# Barebones.net
KiCad netlist of a schematic drawn in EAGLE
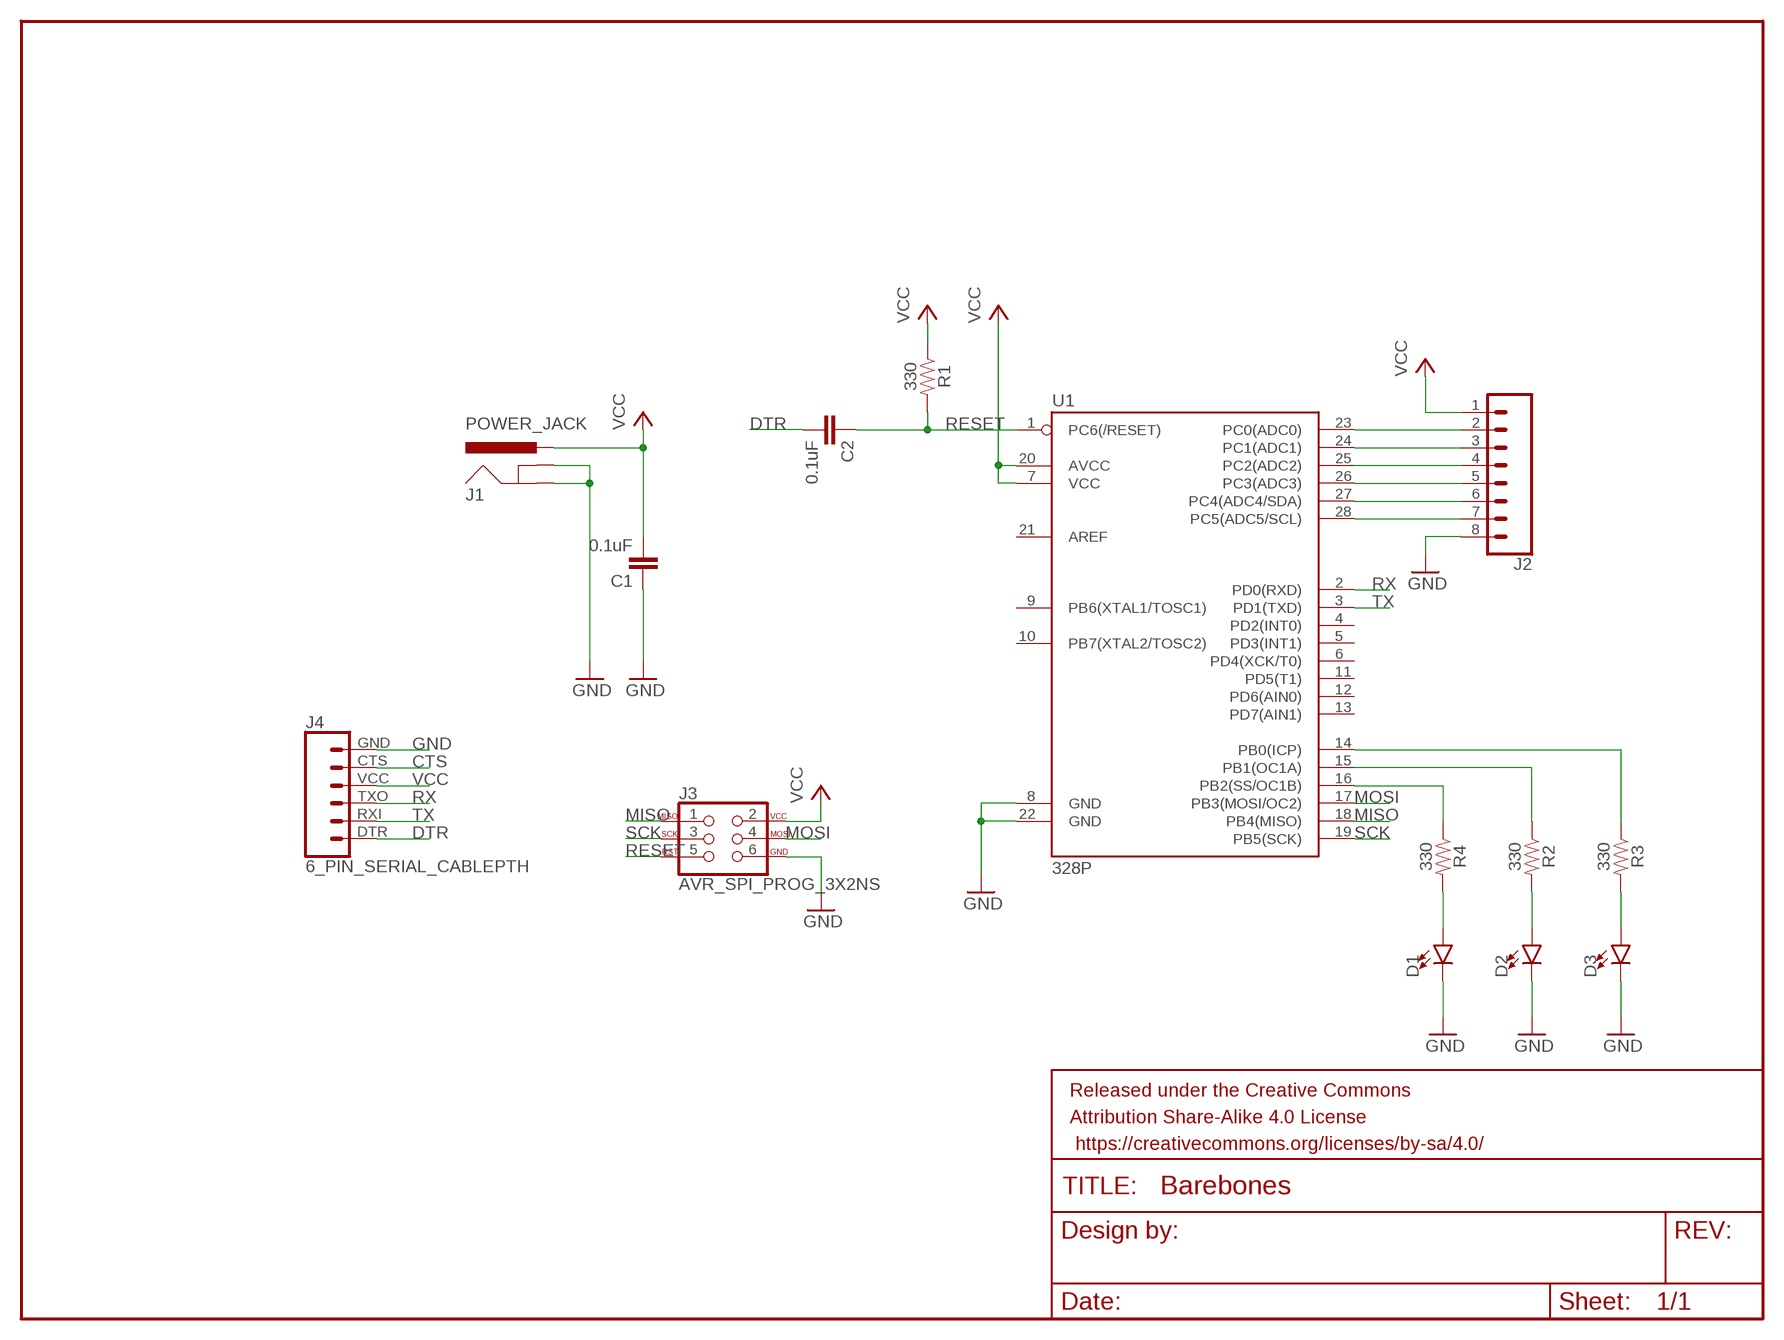
[diagram p0: schematic, sheet 1]

(export (version "E")
  (design (tool "Eeschema 10.0.6"))
  (components
    (comp (ref "C1")
      (value "0.1uF")
      (footprint "eagle-import:CAP-PTH-SMALL-KIT")
      (libsource (lib "eagle-import") (part "0.1UF-KIT-EZ-50V-20%"))
    )
    (comp (ref "C2")
      (value "0.1uF")
      (footprint "eagle-import:CAP-PTH-SMALL-KIT")
      (libsource (lib "eagle-import") (part "0.1UF-KIT-EZ-50V-20%"))
    )
    (comp (ref "D1")
      (value "LED5MM")
      (footprint "eagle-import:LED_5MM")
      (libsource (lib "eagle-import") (part "LED5MM"))
    )
    (comp (ref "D2")
      (value "LED5MM")
      (footprint "eagle-import:LED_5MM")
      (libsource (lib "eagle-import") (part "LED5MM"))
    )
    (comp (ref "D3")
      (value "LED5MM")
      (footprint "eagle-import:LED_5MM")
      (libsource (lib "eagle-import") (part "LED5MM"))
    )
    (comp (ref "FRAME1")
      (value "FRAME-LETTER")
      (footprint "eagle-import:CREATIVE_COMMONS")
      (libsource (lib "eagle-import") (part "FRAME-LETTER"))
    )
    (comp (ref "J1")
      (value "POWER_JACK")
      (footprint "eagle-import:POWER_JACK_PTH")
      (libsource (lib "eagle-import") (part "POWER_JACK"))
    )
    (comp (ref "J2")
      (value "CONN_08\"")
      (footprint "eagle-import:1X08")
      (libsource (lib "eagle-import") (part "CONN_08{dblquote}"))
    )
    (comp (ref "J3")
      (value "AVR_SPI_PROG_3X2NS")
      (footprint "eagle-import:2X3-NS")
      (libsource (lib "eagle-import") (part "AVR_SPI_PROG_3X2NS"))
    )
    (comp (ref "J4")
      (value "6_PIN_SERIAL_CABLEPTH")
      (footprint "eagle-import:FTDI_BASIC")
      (libsource (lib "eagle-import") (part "6_PIN_SERIAL_CABLEPTH"))
    )
    (comp (ref "R1")
      (value "330")
      (footprint "eagle-import:AXIAL-0.3")
      (libsource (lib "eagle-import") (part "330OHM-HORIZ-1/10W-5%"))
    )
    (comp (ref "R2")
      (value "330")
      (footprint "eagle-import:AXIAL-0.3")
      (libsource (lib "eagle-import") (part "330OHM-HORIZ-1/10W-5%"))
    )
    (comp (ref "R3")
      (value "330")
      (footprint "eagle-import:AXIAL-0.3")
      (libsource (lib "eagle-import") (part "330OHM-HORIZ-1/10W-5%"))
    )
    (comp (ref "R4")
      (value "330")
      (footprint "eagle-import:AXIAL-0.3")
      (libsource (lib "eagle-import") (part "330OHM-HORIZ-1/10W-5%"))
    )
    (comp (ref "U1")
      (value "328P")
      (footprint "eagle-import:DIP28")
      (libsource (lib "eagle-import") (part "ATMEGA328P_PDIP"))
    )
  )
  (nets
    (net (code "1") (name "/CTS") (class "Default")
      (node (ref "J4") (pin "CTS") (pinfunction "5_CTS") (pintype "passive"))
    )
    (net (code "2") (name "/DTR") (class "Default")
      (node (ref "C2") (pin "2") (pinfunction "2_2") (pintype "passive"))
      (node (ref "J4") (pin "DTR") (pinfunction "1_DTR") (pintype "passive"))
    )
    (net (code "3") (name "/MISO") (class "Default")
      (node (ref "J3") (pin "1") (pinfunction "1_1") (pintype "passive"))
      (node (ref "U1") (pin "18") (pinfunction "PB4(MISO)_18") (pintype "bidirectional"))
    )
    (net (code "4") (name "/MOSI") (class "Default")
      (node (ref "J3") (pin "4") (pinfunction "4_4") (pintype "passive"))
      (node (ref "U1") (pin "17") (pinfunction "PB3(MOSI/OC2)_17") (pintype "bidirectional"))
    )
    (net (code "5") (name "/RESET") (class "Default")
      (node (ref "C2") (pin "1") (pinfunction "1_1") (pintype "passive"))
      (node (ref "J3") (pin "5") (pinfunction "5_5") (pintype "passive"))
      (node (ref "R1") (pin "P$2") (pinfunction "2_P$2") (pintype "passive"))
      (node (ref "U1") (pin "1") (pinfunction "PC6(/RESET)_1") (pintype "bidirectional"))
    )
    (net (code "6") (name "/RX") (class "Default")
      (node (ref "J4") (pin "TXO") (pinfunction "3_TXO") (pintype "passive"))
      (node (ref "U1") (pin "2") (pinfunction "PD0(RXD)_2") (pintype "bidirectional"))
    )
    (net (code "7") (name "/SCK") (class "Default")
      (node (ref "J3") (pin "3") (pinfunction "3_3") (pintype "passive"))
      (node (ref "U1") (pin "19") (pinfunction "PB5(SCK)_19") (pintype "bidirectional"))
    )
    (net (code "8") (name "/TX") (class "Default")
      (node (ref "J4") (pin "RXI") (pinfunction "2_RXI") (pintype "passive"))
      (node (ref "U1") (pin "3") (pinfunction "PD1(TXD)_3") (pintype "bidirectional"))
    )
    (net (code "9") (name "GND") (class "Default")
      (node (ref "C1") (pin "1") (pinfunction "1_1") (pintype "passive"))
      (node (ref "D1") (pin "K") (pinfunction "C_K") (pintype "passive"))
      (node (ref "D2") (pin "K") (pinfunction "C_K") (pintype "passive"))
      (node (ref "D3") (pin "K") (pinfunction "C_K") (pintype "passive"))
      (node (ref "J1") (pin "GND") (pinfunction "GND_GND") (pintype "bidirectional"))
      (node (ref "J1") (pin "GNDBREAK") (pinfunction "GNDBREAK_GNDBREAK") (pintype "bidirectional"))
      (node (ref "J2") (pin "8") (pinfunction "8_8") (pintype "passive"))
      (node (ref "J3") (pin "6") (pinfunction "6_6") (pintype "passive"))
      (node (ref "J4") (pin "GND") (pinfunction "6_GND") (pintype "passive"))
      (node (ref "U1") (pin "22") (pinfunction "GND_22") (pintype "bidirectional"))
      (node (ref "U1") (pin "8") (pinfunction "GND_8") (pintype "bidirectional"))
    )
    (net (code "10") (name "Net-(R2-1)") (class "Default")
      (node (ref "R2") (pin "P$1") (pinfunction "1_P$1") (pintype "passive"))
      (node (ref "U1") (pin "15") (pinfunction "PB1(OC1A)_15") (pintype "bidirectional"))
    )
    (net (code "11") (name "Net-(R2-2)") (class "Default")
      (node (ref "D2") (pin "A") (pinfunction "A_A") (pintype "passive"))
      (node (ref "R2") (pin "P$2") (pinfunction "2_P$2") (pintype "passive"))
    )
    (net (code "12") (name "Net-(R3-1)") (class "Default")
      (node (ref "R3") (pin "P$1") (pinfunction "1_P$1") (pintype "passive"))
      (node (ref "U1") (pin "14") (pinfunction "PB0(ICP)_14") (pintype "bidirectional"))
    )
    (net (code "13") (name "Net-(R3-2)") (class "Default")
      (node (ref "D3") (pin "A") (pinfunction "A_A") (pintype "passive"))
      (node (ref "R3") (pin "P$2") (pinfunction "2_P$2") (pintype "passive"))
    )
    (net (code "14") (name "Net-(R4-1)") (class "Default")
      (node (ref "R4") (pin "P$1") (pinfunction "1_P$1") (pintype "passive"))
      (node (ref "U1") (pin "16") (pinfunction "PB2(SS/OC1B)_16") (pintype "bidirectional"))
    )
    (net (code "15") (name "Net-(R4-2)") (class "Default")
      (node (ref "D1") (pin "A") (pinfunction "A_A") (pintype "passive"))
      (node (ref "R4") (pin "P$2") (pinfunction "2_P$2") (pintype "passive"))
    )
    (net (code "16") (name "Net-(U1-PC0(ADC0))") (class "Default")
      (node (ref "J2") (pin "2") (pinfunction "2_2") (pintype "passive"))
      (node (ref "U1") (pin "23") (pinfunction "PC0(ADC0)_23") (pintype "bidirectional"))
    )
    (net (code "17") (name "Net-(U1-PC1(ADC1))") (class "Default")
      (node (ref "J2") (pin "3") (pinfunction "3_3") (pintype "passive"))
      (node (ref "U1") (pin "24") (pinfunction "PC1(ADC1)_24") (pintype "bidirectional"))
    )
    (net (code "18") (name "Net-(U1-PC2(ADC2))") (class "Default")
      (node (ref "J2") (pin "4") (pinfunction "4_4") (pintype "passive"))
      (node (ref "U1") (pin "25") (pinfunction "PC2(ADC2)_25") (pintype "bidirectional"))
    )
    (net (code "19") (name "Net-(U1-PC3(ADC3))") (class "Default")
      (node (ref "J2") (pin "5") (pinfunction "5_5") (pintype "passive"))
      (node (ref "U1") (pin "26") (pinfunction "PC3(ADC3)_26") (pintype "bidirectional"))
    )
    (net (code "20") (name "Net-(U1-PC4(ADC4{slash}SDA))") (class "Default")
      (node (ref "J2") (pin "6") (pinfunction "6_6") (pintype "passive"))
      (node (ref "U1") (pin "27") (pinfunction "PC4(ADC4/SDA)_27") (pintype "bidirectional"))
    )
    (net (code "21") (name "Net-(U1-PC5(ADC5{slash}SCL))") (class "Default")
      (node (ref "J2") (pin "7") (pinfunction "7_7") (pintype "passive"))
      (node (ref "U1") (pin "28") (pinfunction "PC5(ADC5/SCL)_28") (pintype "bidirectional"))
    )
    (net (code "22") (name "VCC") (class "Default")
      (node (ref "C1") (pin "2") (pinfunction "2_2") (pintype "passive"))
      (node (ref "J1") (pin "PWR") (pinfunction "PWR_PWR") (pintype "bidirectional"))
      (node (ref "J2") (pin "1") (pinfunction "1_1") (pintype "passive"))
      (node (ref "J3") (pin "2") (pinfunction "2_2") (pintype "passive"))
      (node (ref "J4") (pin "VCC") (pinfunction "4_VCC") (pintype "passive"))
      (node (ref "R1") (pin "P$1") (pinfunction "1_P$1") (pintype "passive"))
      (node (ref "U1") (pin "20") (pinfunction "AVCC_20") (pintype "bidirectional"))
      (node (ref "U1") (pin "7") (pinfunction "VCC_7") (pintype "bidirectional"))
    )
    (net (code "23") (name "unconnected-(U1-AREF-Pad21)") (class "Default")
      (node (ref "U1") (pin "21") (pinfunction "AREF_21") (pintype "bidirectional"))
    )
    (net (code "24") (name "unconnected-(U1-PB6(XTAL1{slash}TOSC1)-Pad9)") (class "Default")
      (node (ref "U1") (pin "9") (pinfunction "PB6(XTAL1/TOSC1)_9") (pintype "bidirectional"))
    )
    (net (code "25") (name "unconnected-(U1-PB7(XTAL2{slash}TOSC2)-Pad10)") (class "Default")
      (node (ref "U1") (pin "10") (pinfunction "PB7(XTAL2/TOSC2)_10") (pintype "bidirectional"))
    )
    (net (code "26") (name "unconnected-(U1-PD2(INT0)-Pad4)") (class "Default")
      (node (ref "U1") (pin "4") (pinfunction "PD2(INT0)_4") (pintype "bidirectional"))
    )
    (net (code "27") (name "unconnected-(U1-PD3(INT1)-Pad5)") (class "Default")
      (node (ref "U1") (pin "5") (pinfunction "PD3(INT1)_5") (pintype "bidirectional"))
    )
    (net (code "28") (name "unconnected-(U1-PD4(XCK{slash}T0)-Pad6)") (class "Default")
      (node (ref "U1") (pin "6") (pinfunction "PD4(XCK/T0)_6") (pintype "bidirectional"))
    )
    (net (code "29") (name "unconnected-(U1-PD5(T1)-Pad11)") (class "Default")
      (node (ref "U1") (pin "11") (pinfunction "PD5(T1)_11") (pintype "bidirectional"))
    )
    (net (code "30") (name "unconnected-(U1-PD6(AIN0)-Pad12)") (class "Default")
      (node (ref "U1") (pin "12") (pinfunction "PD6(AIN0)_12") (pintype "bidirectional"))
    )
    (net (code "31") (name "unconnected-(U1-PD7(AIN1)-Pad13)") (class "Default")
      (node (ref "U1") (pin "13") (pinfunction "PD7(AIN1)_13") (pintype "bidirectional"))
    )
  )
)
